# hexagon.net
KiCad netlist of a schematic drawn in EAGLE
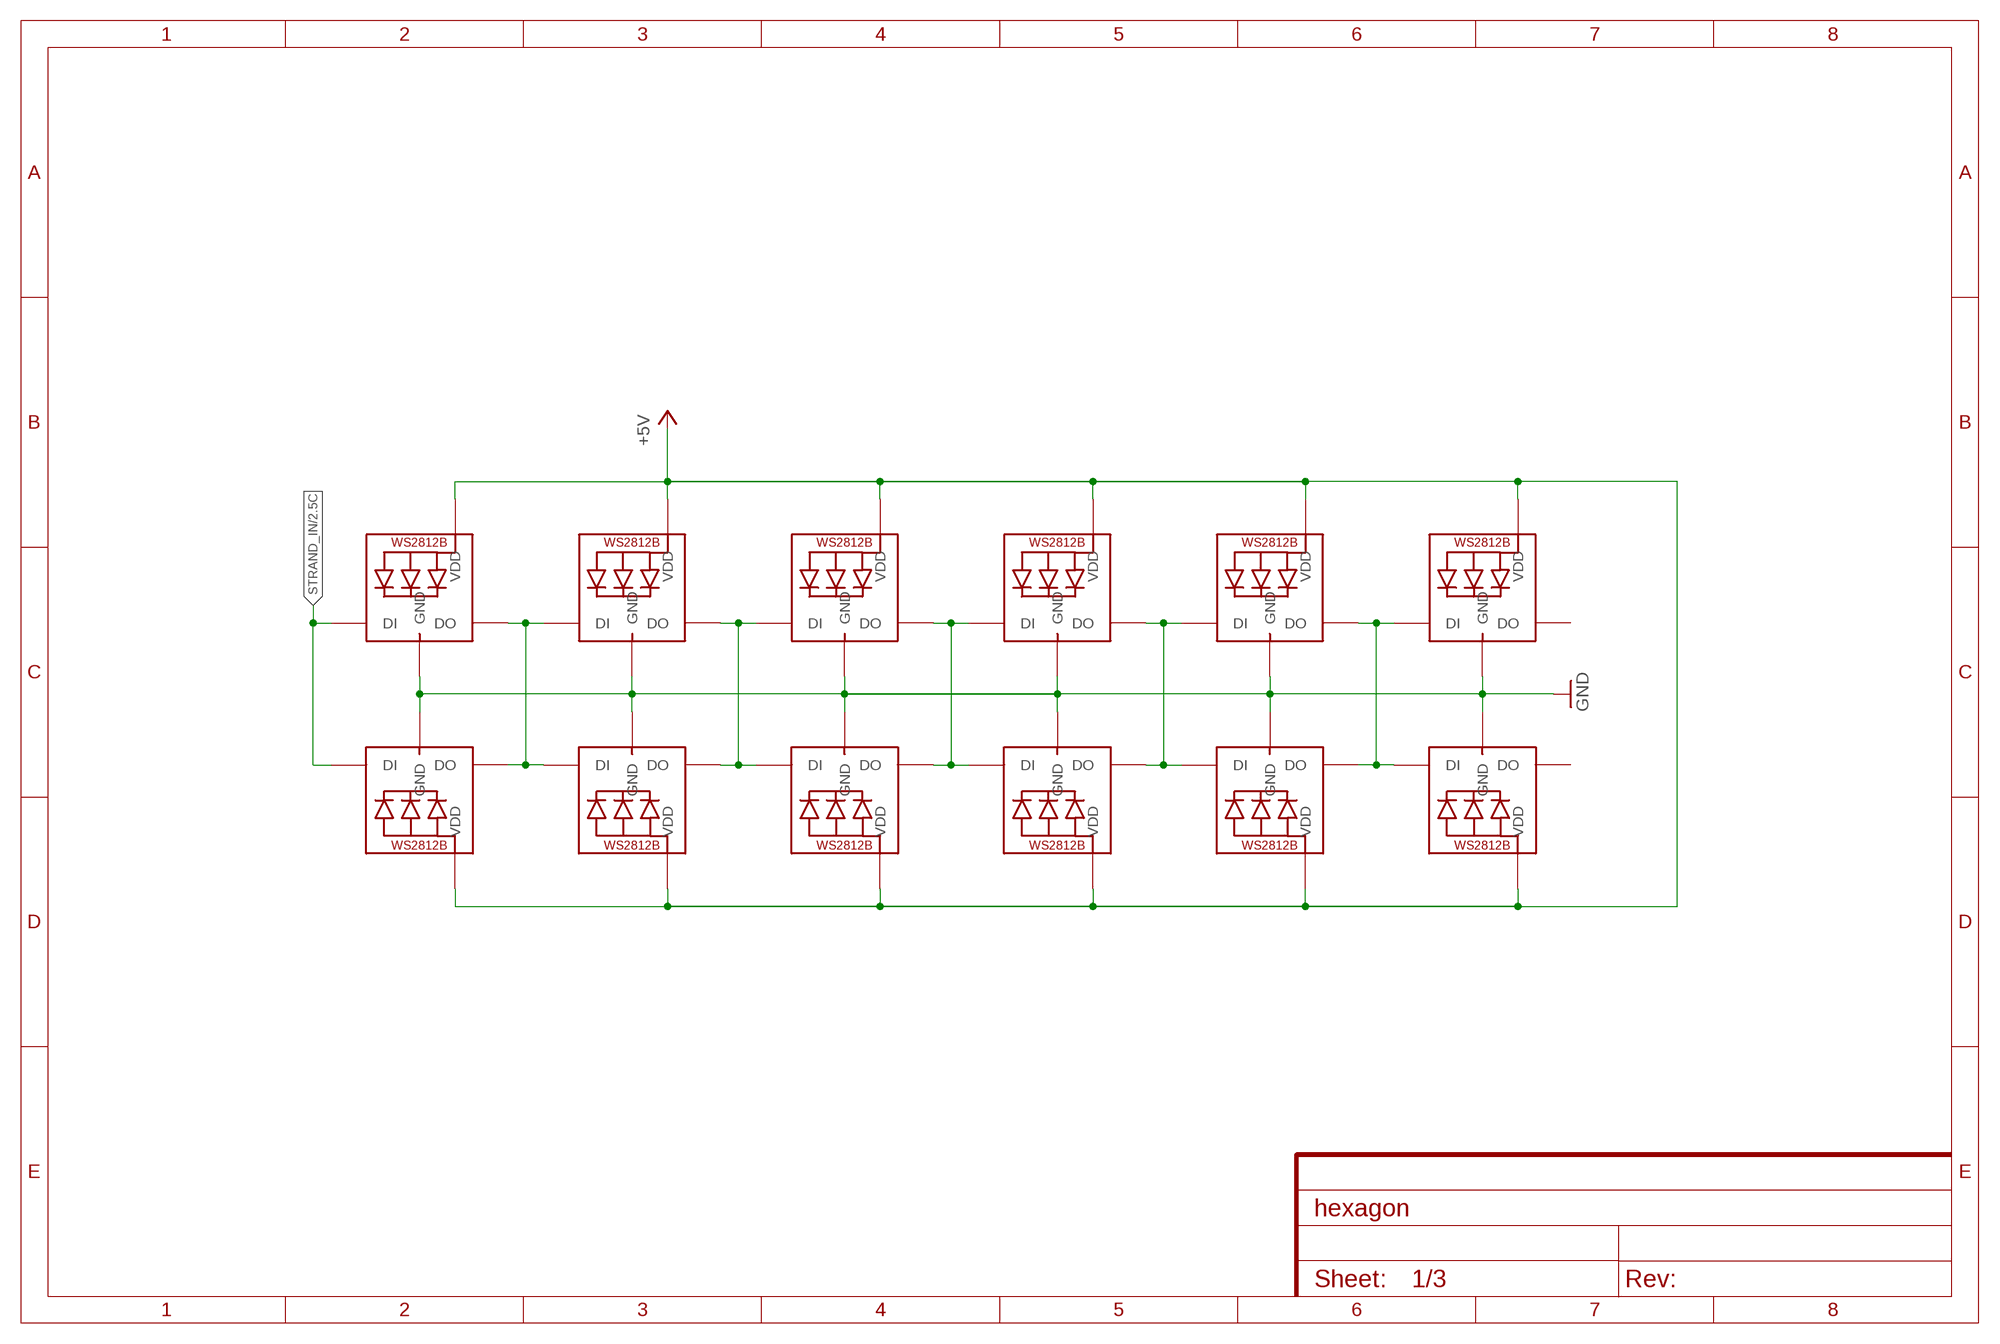
[diagram p0: schematic, sheet 1]
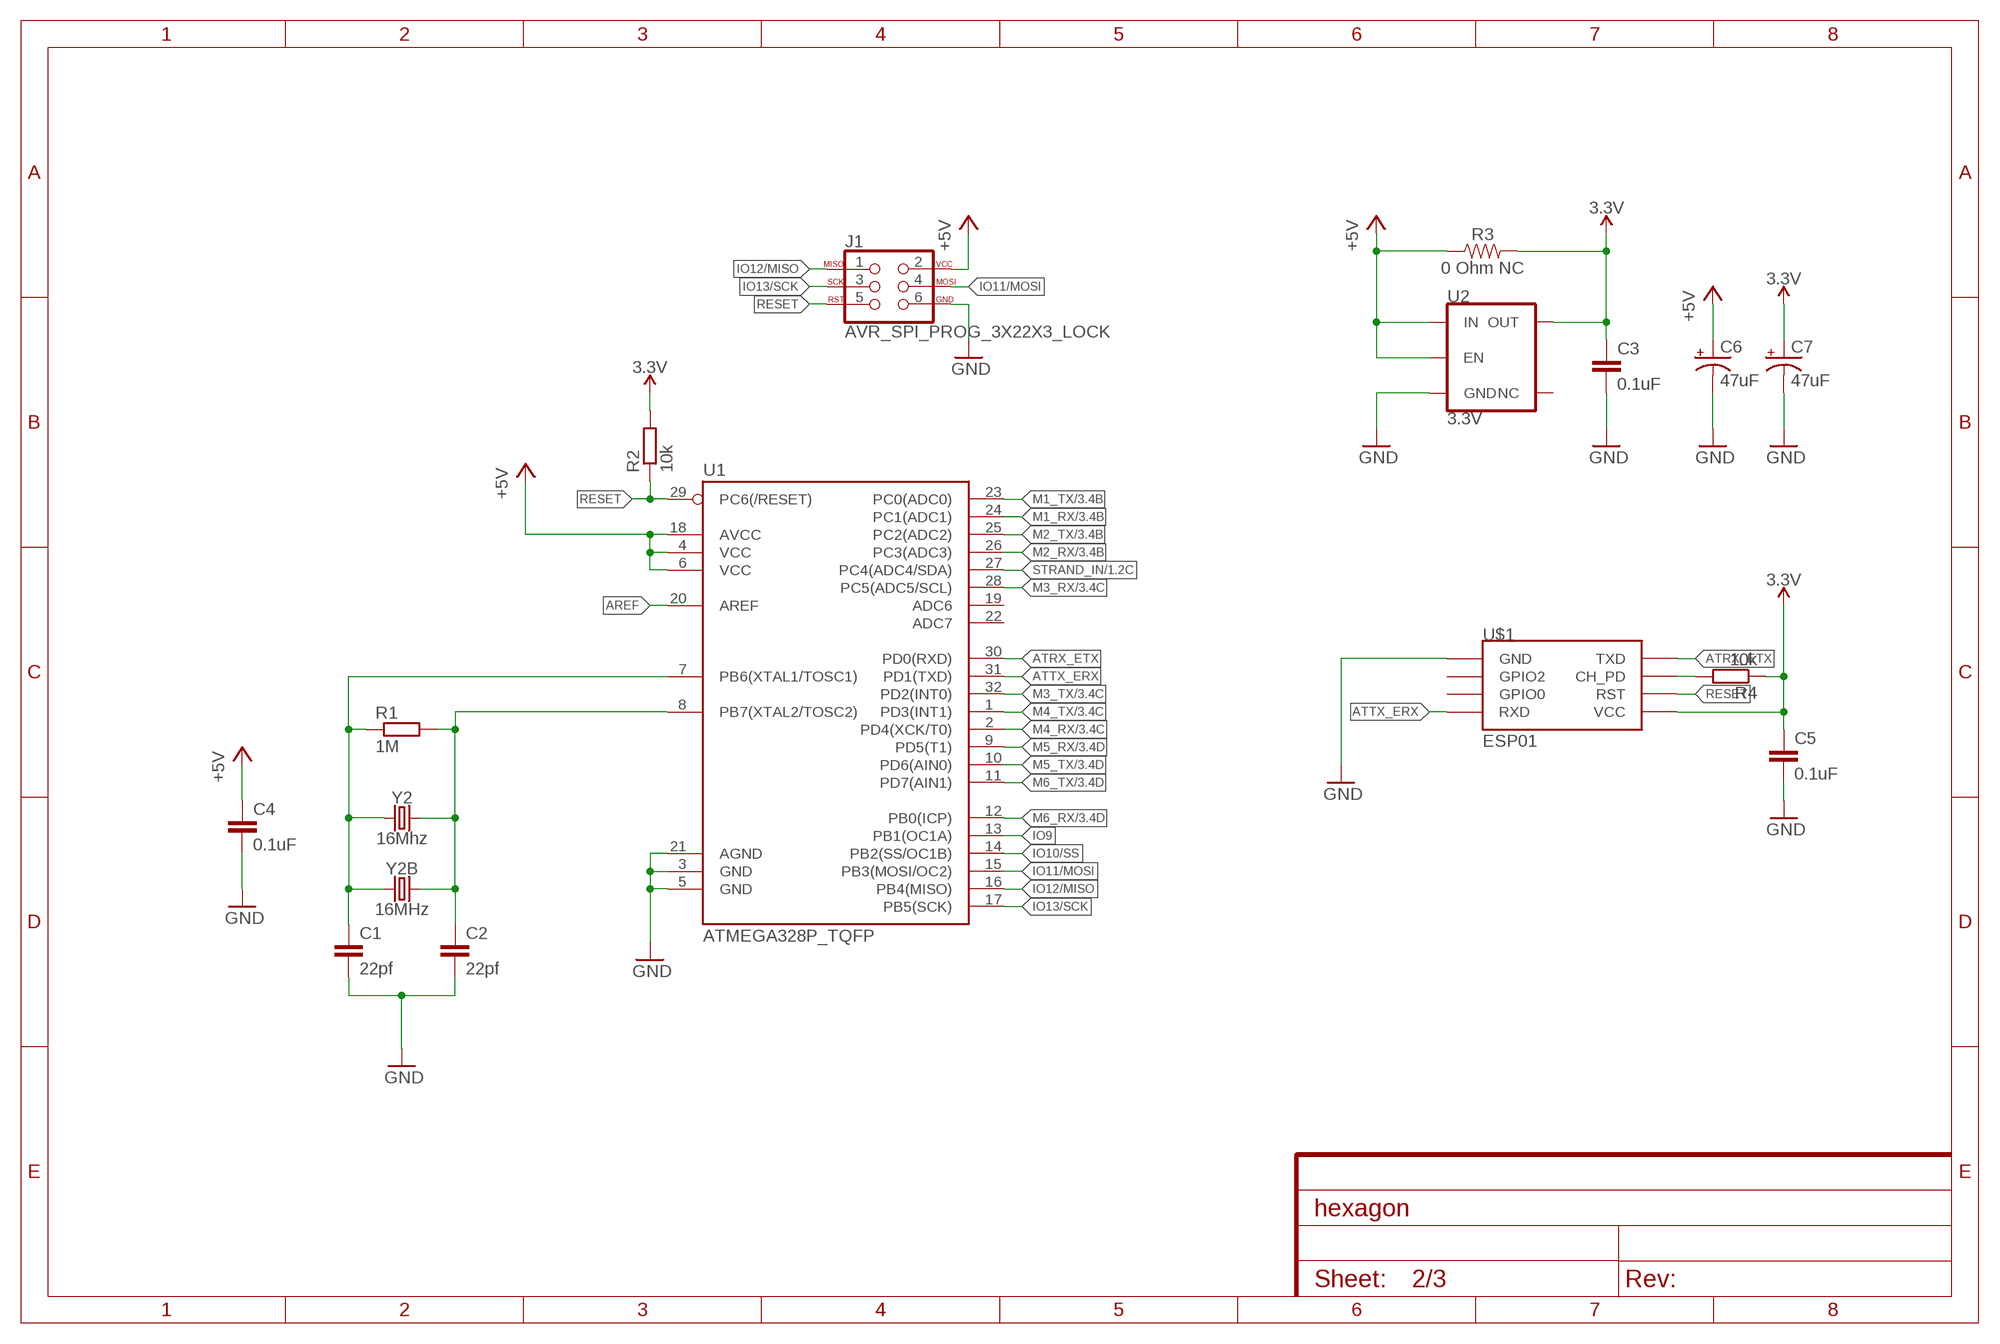
[diagram p1: schematic, sheet 2]
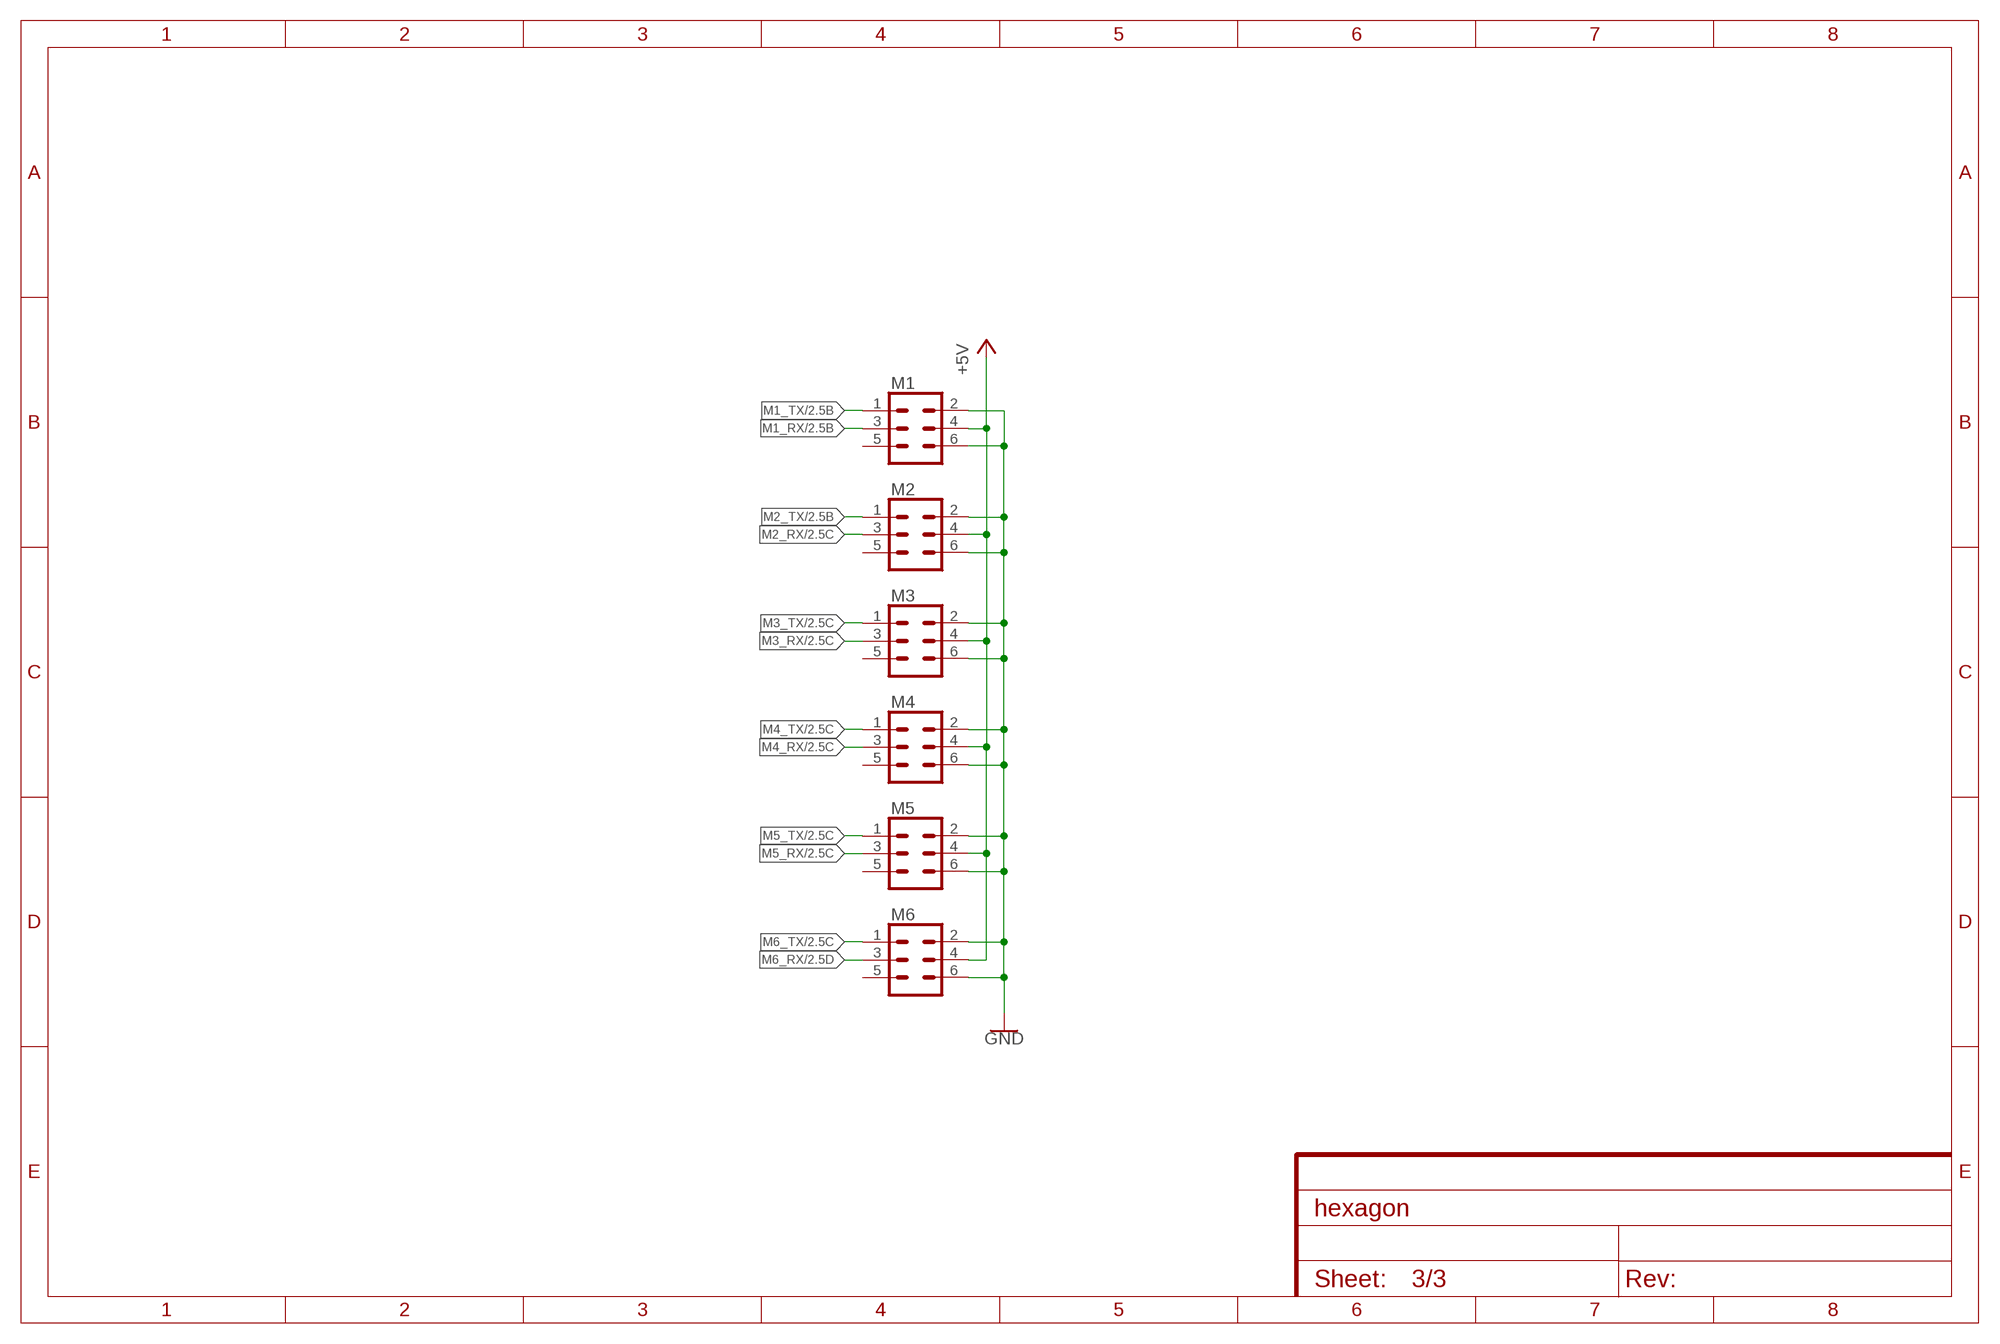
[diagram p2: schematic, sheet 3]

(export (version "E")
  (design (tool "Eeschema 10.0.6"))
  (components
    (comp (ref "C1")
      (value "22pf")
      (footprint "eagle-import:C0603")
      (libsource (lib "eagle-import") (part "C-EUC0603"))
    )
    (comp (ref "C2")
      (value "22pf")
      (footprint "eagle-import:C0603")
      (libsource (lib "eagle-import") (part "C-EUC0603"))
    )
    (comp (ref "C3")
      (value "0.1uF")
      (footprint "eagle-import:C0603")
      (libsource (lib "eagle-import") (part "C-EUC0603"))
    )
    (comp (ref "C4")
      (value "0.1uF")
      (footprint "eagle-import:C0603")
      (libsource (lib "eagle-import") (part "C-EUC0603"))
    )
    (comp (ref "C5")
      (value "0.1uF")
      (footprint "eagle-import:C0603")
      (libsource (lib "eagle-import") (part "C-EUC0603"))
    )
    (comp (ref "C6")
      (value "47uF")
      (footprint "eagle-import:PANASONIC_D")
      (libsource (lib "eagle-import") (part "47UF-POLAR-PANASONIC_D-35V-20%"))
    )
    (comp (ref "C7")
      (value "47uF")
      (footprint "eagle-import:PANASONIC_D")
      (libsource (lib "eagle-import") (part "47UF-POLAR-PANASONIC_D-35V-20%"))
    )
    (comp (ref "J1")
      (value "AVR_SPI_PROG_3X22X3_LOCK")
      (footprint "eagle-import:2X3_LOCK")
      (libsource (lib "eagle-import") (part "AVR_SPI_PROG_3X22X3_LOCK"))
    )
    (comp (ref "R1")
      (value "1M")
      (footprint "eagle-import:R0603")
      (libsource (lib "eagle-import") (part "R-EU_R0603"))
    )
    (comp (ref "R2")
      (value "10k")
      (footprint "eagle-import:R0603")
      (libsource (lib "eagle-import") (part "R-EU_R0603"))
    )
    (comp (ref "R3")
      (value "0 Ohm NC")
      (footprint "eagle-import:0603")
      (libsource (lib "eagle-import") (part "RESISTOR0603"))
    )
    (comp (ref "R4")
      (value "10k")
      (footprint "eagle-import:R0603")
      (libsource (lib "eagle-import") (part "R-EU_R0603"))
    )
    (comp (ref "U$1")
      (value "ESP01")
      (footprint "eagle-import:ESP01")
      (libsource (lib "eagle-import") (part "ESP01"))
    )
    (comp (ref "U1")
      (value "ATMEGA328P_TQFP")
      (footprint "eagle-import:TQFP32-08")
      (libsource (lib "eagle-import") (part "ATMEGA328P_TQFP"))
    )
    (comp (ref "U2")
      (value "3.3V")
      (footprint "eagle-import:SOT23-5")
      (libsource (lib "eagle-import") (part "V_REG_AP2112K-3.3V"))
    )
    (comp (ref "Y2")
      (value "16Mhz")
      (footprint "eagle-import:HC49UP")
      (libsource (lib "eagle-import") (part "CRYSTAL-8MHZSMD-HC49UP"))
    )
    (comp (ref "Y2B")
      (value "16MHz")
      (footprint "eagle-import:HC49U")
      (libsource (lib "eagle-import") (part "CRYSTALPTH-HC49UV"))
    )
    (comp (ref "M1")
      (value "CONN_03X2SHROUD")
      (footprint "eagle-import:2X3-SHROUDED")
      (libsource (lib "eagle-import") (part "CONN_03X2SHROUD"))
    )
    (comp (ref "M2")
      (value "CONN_03X2SHROUD")
      (footprint "eagle-import:2X3-SHROUDED")
      (libsource (lib "eagle-import") (part "CONN_03X2SHROUD"))
    )
    (comp (ref "M3")
      (value "CONN_03X2SHROUD")
      (footprint "eagle-import:2X3-SHROUDED")
      (libsource (lib "eagle-import") (part "CONN_03X2SHROUD"))
    )
    (comp (ref "M4")
      (value "CONN_03X2SHROUD")
      (footprint "eagle-import:2X3-SHROUDED")
      (libsource (lib "eagle-import") (part "CONN_03X2SHROUD"))
    )
    (comp (ref "M5")
      (value "CONN_03X2SHROUD")
      (footprint "eagle-import:2X3-SHROUDED")
      (libsource (lib "eagle-import") (part "CONN_03X2SHROUD"))
    )
    (comp (ref "M6")
      (value "CONN_03X2SHROUD")
      (footprint "eagle-import:2X3-SHROUDED")
      (libsource (lib "eagle-import") (part "CONN_03X2SHROUD"))
    )
    (comp (ref "LED1")
      (value "WS2812B5050")
      (footprint "eagle-import:WS2812B")
      (libsource (lib "eagle-import") (part "WS2812B5050"))
    )
    (comp (ref "LED2")
      (value "WS2812B5050")
      (footprint "eagle-import:WS2812B")
      (libsource (lib "eagle-import") (part "WS2812B5050"))
    )
    (comp (ref "LED3")
      (value "WS2812B5050")
      (footprint "eagle-import:WS2812B")
      (libsource (lib "eagle-import") (part "WS2812B5050"))
    )
    (comp (ref "LED4")
      (value "WS2812B5050")
      (footprint "eagle-import:WS2812B")
      (libsource (lib "eagle-import") (part "WS2812B5050"))
    )
    (comp (ref "LED5")
      (value "WS2812B5050")
      (footprint "eagle-import:WS2812B")
      (libsource (lib "eagle-import") (part "WS2812B5050"))
    )
    (comp (ref "LED6")
      (value "WS2812B5050")
      (footprint "eagle-import:WS2812B")
      (libsource (lib "eagle-import") (part "WS2812B5050"))
    )
    (comp (ref "LED7")
      (value "WS2812B3535")
      (footprint "eagle-import:LED3535")
      (libsource (lib "eagle-import") (part "WS2812B3535"))
    )
    (comp (ref "LED8")
      (value "WS2812B3535")
      (footprint "eagle-import:LED3535")
      (libsource (lib "eagle-import") (part "WS2812B3535"))
    )
    (comp (ref "LED9")
      (value "WS2812B3535")
      (footprint "eagle-import:LED3535")
      (libsource (lib "eagle-import") (part "WS2812B3535"))
    )
    (comp (ref "LED10")
      (value "WS2812B3535")
      (footprint "eagle-import:LED3535")
      (libsource (lib "eagle-import") (part "WS2812B3535"))
    )
    (comp (ref "LED11")
      (value "WS2812B3535")
      (footprint "eagle-import:LED3535")
      (libsource (lib "eagle-import") (part "WS2812B3535"))
    )
    (comp (ref "LED12")
      (value "WS2812B3535")
      (footprint "eagle-import:LED3535")
      (libsource (lib "eagle-import") (part "WS2812B3535"))
    )
  )
  (nets
    (net (code "1") (name "+5V") (class "Default")
      (node (ref "C4") (pin "1") (pinfunction "1_1") (pintype "passive"))
      (node (ref "C6") (pin "+") (pinfunction "+_+") (pintype "passive"))
      (node (ref "J1") (pin "2") (pinfunction "2_2") (pintype "passive"))
      (node (ref "LED1") (pin "1-VDD") (pinfunction "VDD_1-VDD") (pintype "power_in"))
      (node (ref "LED10") (pin "2") (pinfunction "VDD_2") (pintype "power_in"))
      (node (ref "LED11") (pin "2") (pinfunction "VDD_2") (pintype "power_in"))
      (node (ref "LED12") (pin "2") (pinfunction "VDD_2") (pintype "power_in"))
      (node (ref "LED2") (pin "1-VDD") (pinfunction "VDD_1-VDD") (pintype "power_in"))
      (node (ref "LED3") (pin "1-VDD") (pinfunction "VDD_1-VDD") (pintype "power_in"))
      (node (ref "LED4") (pin "1-VDD") (pinfunction "VDD_1-VDD") (pintype "power_in"))
      (node (ref "LED5") (pin "1-VDD") (pinfunction "VDD_1-VDD") (pintype "power_in"))
      (node (ref "LED6") (pin "1-VDD") (pinfunction "VDD_1-VDD") (pintype "power_in"))
      (node (ref "LED7") (pin "2") (pinfunction "VDD_2") (pintype "power_in"))
      (node (ref "LED8") (pin "2") (pinfunction "VDD_2") (pintype "power_in"))
      (node (ref "LED9") (pin "2") (pinfunction "VDD_2") (pintype "power_in"))
      (node (ref "M1") (pin "4") (pinfunction "4_4") (pintype "bidirectional"))
      (node (ref "M2") (pin "4") (pinfunction "4_4") (pintype "bidirectional"))
      (node (ref "M3") (pin "4") (pinfunction "4_4") (pintype "bidirectional"))
      (node (ref "M4") (pin "4") (pinfunction "4_4") (pintype "bidirectional"))
      (node (ref "M5") (pin "4") (pinfunction "4_4") (pintype "bidirectional"))
      (node (ref "M6") (pin "4") (pinfunction "4_4") (pintype "bidirectional"))
      (node (ref "R3") (pin "1") (pinfunction "1_1") (pintype "passive"))
      (node (ref "U1") (pin "18") (pinfunction "AVCC_18") (pintype "bidirectional"))
      (node (ref "U1") (pin "4") (pinfunction "VCC_4") (pintype "bidirectional"))
      (node (ref "U1") (pin "6") (pinfunction "VCC_6") (pintype "bidirectional"))
      (node (ref "U2") (pin "1") (pinfunction "IN_1") (pintype "input"))
      (node (ref "U2") (pin "3") (pinfunction "EN_3") (pintype "input"))
    )
    (net (code "2") (name "3.3V") (class "Default")
      (node (ref "C3") (pin "1") (pinfunction "1_1") (pintype "passive"))
      (node (ref "C5") (pin "1") (pinfunction "1_1") (pintype "passive"))
      (node (ref "C7") (pin "+") (pinfunction "+_+") (pintype "passive"))
      (node (ref "R2") (pin "2") (pinfunction "2_2") (pintype "passive"))
      (node (ref "R3") (pin "2") (pinfunction "2_2") (pintype "passive"))
      (node (ref "R4") (pin "1") (pinfunction "1_1") (pintype "passive"))
      (node (ref "U$1") (pin "VCC") (pinfunction "VCC_VCC") (pintype "bidirectional"))
      (node (ref "U2") (pin "5") (pinfunction "OUT_5") (pintype "passive"))
    )
    (net (code "3") (name "AREF") (class "Default")
      (node (ref "U1") (pin "20") (pinfunction "AREF_20") (pintype "bidirectional"))
    )
    (net (code "4") (name "ATRX_ETX") (class "Default")
      (node (ref "U$1") (pin "TX") (pinfunction "TXD_TX") (pintype "bidirectional"))
      (node (ref "U1") (pin "30") (pinfunction "PD0(RXD)_30") (pintype "bidirectional"))
    )
    (net (code "5") (name "ATTX_ERX") (class "Default")
      (node (ref "U$1") (pin "RX") (pinfunction "RXD_RX") (pintype "bidirectional"))
      (node (ref "U1") (pin "31") (pinfunction "PD1(TXD)_31") (pintype "bidirectional"))
    )
    (net (code "6") (name "GND") (class "Default")
      (node (ref "C1") (pin "2") (pinfunction "2_2") (pintype "passive"))
      (node (ref "C2") (pin "2") (pinfunction "2_2") (pintype "passive"))
      (node (ref "C3") (pin "2") (pinfunction "2_2") (pintype "passive"))
      (node (ref "C4") (pin "2") (pinfunction "2_2") (pintype "passive"))
      (node (ref "C5") (pin "2") (pinfunction "2_2") (pintype "passive"))
      (node (ref "C6") (pin "-") (pinfunction "-_-") (pintype "passive"))
      (node (ref "C7") (pin "-") (pinfunction "-_-") (pintype "passive"))
      (node (ref "J1") (pin "6") (pinfunction "6_6") (pintype "passive"))
      (node (ref "LED1") (pin "3-GND") (pinfunction "GND_3-GND") (pintype "power_in"))
      (node (ref "LED10") (pin "4") (pinfunction "GND_4") (pintype "power_in"))
      (node (ref "LED11") (pin "4") (pinfunction "GND_4") (pintype "power_in"))
      (node (ref "LED12") (pin "4") (pinfunction "GND_4") (pintype "power_in"))
      (node (ref "LED2") (pin "3-GND") (pinfunction "GND_3-GND") (pintype "power_in"))
      (node (ref "LED3") (pin "3-GND") (pinfunction "GND_3-GND") (pintype "power_in"))
      (node (ref "LED4") (pin "3-GND") (pinfunction "GND_3-GND") (pintype "power_in"))
      (node (ref "LED5") (pin "3-GND") (pinfunction "GND_3-GND") (pintype "power_in"))
      (node (ref "LED6") (pin "3-GND") (pinfunction "GND_3-GND") (pintype "power_in"))
      (node (ref "LED7") (pin "4") (pinfunction "GND_4") (pintype "power_in"))
      (node (ref "LED8") (pin "4") (pinfunction "GND_4") (pintype "power_in"))
      (node (ref "LED9") (pin "4") (pinfunction "GND_4") (pintype "power_in"))
      (node (ref "M1") (pin "2") (pinfunction "2_2") (pintype "bidirectional"))
      (node (ref "M1") (pin "6") (pinfunction "6_6") (pintype "bidirectional"))
      (node (ref "M2") (pin "2") (pinfunction "2_2") (pintype "bidirectional"))
      (node (ref "M2") (pin "6") (pinfunction "6_6") (pintype "bidirectional"))
      (node (ref "M3") (pin "2") (pinfunction "2_2") (pintype "bidirectional"))
      (node (ref "M3") (pin "6") (pinfunction "6_6") (pintype "bidirectional"))
      (node (ref "M4") (pin "2") (pinfunction "2_2") (pintype "bidirectional"))
      (node (ref "M4") (pin "6") (pinfunction "6_6") (pintype "bidirectional"))
      (node (ref "M5") (pin "2") (pinfunction "2_2") (pintype "bidirectional"))
      (node (ref "M5") (pin "6") (pinfunction "6_6") (pintype "bidirectional"))
      (node (ref "M6") (pin "2") (pinfunction "2_2") (pintype "bidirectional"))
      (node (ref "M6") (pin "6") (pinfunction "6_6") (pintype "bidirectional"))
      (node (ref "U$1") (pin "GND") (pinfunction "GND_GND") (pintype "bidirectional"))
      (node (ref "U1") (pin "21") (pinfunction "AGND_21") (pintype "bidirectional"))
      (node (ref "U1") (pin "3") (pinfunction "GND_3") (pintype "bidirectional"))
      (node (ref "U1") (pin "5") (pinfunction "GND_5") (pintype "bidirectional"))
      (node (ref "U2") (pin "2") (pinfunction "GND_2") (pintype "input"))
    )
    (net (code "7") (name "IO9") (class "Default")
      (node (ref "U1") (pin "13") (pinfunction "PB1(OC1A)_13") (pintype "bidirectional"))
    )
    (net (code "8") (name "IO10{slash}SS") (class "Default")
      (node (ref "U1") (pin "14") (pinfunction "PB2(SS/OC1B)_14") (pintype "bidirectional"))
    )
    (net (code "9") (name "IO11{slash}MOSI") (class "Default")
      (node (ref "J1") (pin "4") (pinfunction "4_4") (pintype "passive"))
      (node (ref "U1") (pin "15") (pinfunction "PB3(MOSI/OC2)_15") (pintype "bidirectional"))
    )
    (net (code "10") (name "IO12{slash}MISO") (class "Default")
      (node (ref "J1") (pin "1") (pinfunction "1_1") (pintype "passive"))
      (node (ref "U1") (pin "16") (pinfunction "PB4(MISO)_16") (pintype "bidirectional"))
    )
    (net (code "11") (name "IO13{slash}SCK") (class "Default")
      (node (ref "J1") (pin "3") (pinfunction "3_3") (pintype "passive"))
      (node (ref "U1") (pin "17") (pinfunction "PB5(SCK)_17") (pintype "bidirectional"))
    )
    (net (code "12") (name "M1_RX") (class "Default")
      (node (ref "M1") (pin "3") (pinfunction "3_3") (pintype "bidirectional"))
      (node (ref "U1") (pin "24") (pinfunction "PC1(ADC1)_24") (pintype "bidirectional"))
    )
    (net (code "13") (name "M1_TX") (class "Default")
      (node (ref "M1") (pin "1") (pinfunction "1_1") (pintype "bidirectional"))
      (node (ref "U1") (pin "23") (pinfunction "PC0(ADC0)_23") (pintype "bidirectional"))
    )
    (net (code "14") (name "M2_RX") (class "Default")
      (node (ref "M2") (pin "3") (pinfunction "3_3") (pintype "bidirectional"))
      (node (ref "U1") (pin "26") (pinfunction "PC3(ADC3)_26") (pintype "bidirectional"))
    )
    (net (code "15") (name "M2_TX") (class "Default")
      (node (ref "M2") (pin "1") (pinfunction "1_1") (pintype "bidirectional"))
      (node (ref "U1") (pin "25") (pinfunction "PC2(ADC2)_25") (pintype "bidirectional"))
    )
    (net (code "16") (name "M3_RX") (class "Default")
      (node (ref "M3") (pin "3") (pinfunction "3_3") (pintype "bidirectional"))
      (node (ref "U1") (pin "28") (pinfunction "PC5(ADC5/SCL)_28") (pintype "bidirectional"))
    )
    (net (code "17") (name "M3_TX") (class "Default")
      (node (ref "M3") (pin "1") (pinfunction "1_1") (pintype "bidirectional"))
      (node (ref "U1") (pin "32") (pinfunction "PD2(INT0)_32") (pintype "bidirectional"))
    )
    (net (code "18") (name "M4_RX") (class "Default")
      (node (ref "M4") (pin "3") (pinfunction "3_3") (pintype "bidirectional"))
      (node (ref "U1") (pin "2") (pinfunction "PD4(XCK/T0)_2") (pintype "bidirectional"))
    )
    (net (code "19") (name "M4_TX") (class "Default")
      (node (ref "M4") (pin "1") (pinfunction "1_1") (pintype "bidirectional"))
      (node (ref "U1") (pin "1") (pinfunction "PD3(INT1)_1") (pintype "bidirectional"))
    )
    (net (code "20") (name "M5_RX") (class "Default")
      (node (ref "M5") (pin "3") (pinfunction "3_3") (pintype "bidirectional"))
      (node (ref "U1") (pin "9") (pinfunction "PD5(T1)_9") (pintype "bidirectional"))
    )
    (net (code "21") (name "M5_TX") (class "Default")
      (node (ref "M5") (pin "1") (pinfunction "1_1") (pintype "bidirectional"))
      (node (ref "U1") (pin "10") (pinfunction "PD6(AIN0)_10") (pintype "bidirectional"))
    )
    (net (code "22") (name "M6_RX") (class "Default")
      (node (ref "M6") (pin "3") (pinfunction "3_3") (pintype "bidirectional"))
      (node (ref "U1") (pin "12") (pinfunction "PB0(ICP)_12") (pintype "bidirectional"))
    )
    (net (code "23") (name "M6_TX") (class "Default")
      (node (ref "M6") (pin "1") (pinfunction "1_1") (pintype "bidirectional"))
      (node (ref "U1") (pin "11") (pinfunction "PD7(AIN1)_11") (pintype "bidirectional"))
    )
    (net (code "24") (name "Net-(LED1-DI)") (class "Default")
      (node (ref "LED1") (pin "4-DIN") (pinfunction "DI_4-DIN") (pintype "input"))
      (node (ref "LED12") (pin "3") (pinfunction "DO_3") (pintype "output"))
      (node (ref "LED6") (pin "2-DOUT") (pinfunction "DO_2-DOUT") (pintype "output"))
      (node (ref "LED7") (pin "1") (pinfunction "DI_1") (pintype "input"))
    )
    (net (code "25") (name "Net-(LED2-DO)") (class "Default")
      (node (ref "LED2") (pin "2-DOUT") (pinfunction "DO_2-DOUT") (pintype "output"))
      (node (ref "LED3") (pin "4-DIN") (pinfunction "DI_4-DIN") (pintype "input"))
      (node (ref "LED8") (pin "3") (pinfunction "DO_3") (pintype "output"))
      (node (ref "LED9") (pin "1") (pinfunction "DI_1") (pintype "input"))
    )
    (net (code "26") (name "Net-(LED10-DI)") (class "Default")
      (node (ref "LED10") (pin "1") (pinfunction "DI_1") (pintype "input"))
      (node (ref "LED3") (pin "2-DOUT") (pinfunction "DO_2-DOUT") (pintype "output"))
      (node (ref "LED4") (pin "4-DIN") (pinfunction "DI_4-DIN") (pintype "input"))
      (node (ref "LED9") (pin "3") (pinfunction "DO_3") (pintype "output"))
    )
    (net (code "27") (name "Net-(LED10-DO)") (class "Default")
      (node (ref "LED10") (pin "3") (pinfunction "DO_3") (pintype "output"))
      (node (ref "LED11") (pin "1") (pinfunction "DI_1") (pintype "input"))
      (node (ref "LED4") (pin "2-DOUT") (pinfunction "DO_2-DOUT") (pintype "output"))
      (node (ref "LED5") (pin "4-DIN") (pinfunction "DI_4-DIN") (pintype "input"))
    )
    (net (code "28") (name "Net-(LED11-DO)") (class "Default")
      (node (ref "LED11") (pin "3") (pinfunction "DO_3") (pintype "output"))
      (node (ref "LED12") (pin "1") (pinfunction "DI_1") (pintype "input"))
      (node (ref "LED5") (pin "2-DOUT") (pinfunction "DO_2-DOUT") (pintype "output"))
      (node (ref "LED6") (pin "4-DIN") (pinfunction "DI_4-DIN") (pintype "input"))
    )
    (net (code "29") (name "Net-(R4-Pad2)") (class "Default")
      (node (ref "R4") (pin "2") (pinfunction "2_2") (pintype "passive"))
      (node (ref "U$1") (pin "CH_PD") (pinfunction "CH_PD_CH_PD") (pintype "bidirectional"))
    )
    (net (code "30") (name "Net-(U1-PB6(XTAL1{slash}TOSC1))") (class "Default")
      (node (ref "C1") (pin "1") (pinfunction "1_1") (pintype "passive"))
      (node (ref "R1") (pin "1") (pinfunction "1_1") (pintype "passive"))
      (node (ref "U1") (pin "7") (pinfunction "PB6(XTAL1/TOSC1)_7") (pintype "bidirectional"))
      (node (ref "Y2") (pin "1") (pinfunction "1_1") (pintype "passive"))
      (node (ref "Y2B") (pin "1") (pinfunction "1_1") (pintype "passive"))
    )
    (net (code "31") (name "Net-(U1-PB7(XTAL2{slash}TOSC2))") (class "Default")
      (node (ref "C2") (pin "1") (pinfunction "1_1") (pintype "passive"))
      (node (ref "R1") (pin "2") (pinfunction "2_2") (pintype "passive"))
      (node (ref "U1") (pin "8") (pinfunction "PB7(XTAL2/TOSC2)_8") (pintype "bidirectional"))
      (node (ref "Y2") (pin "2") (pinfunction "2_2") (pintype "passive"))
      (node (ref "Y2B") (pin "2") (pinfunction "2_2") (pintype "passive"))
    )
    (net (code "32") (name "RESET") (class "Default")
      (node (ref "J1") (pin "5") (pinfunction "5_5") (pintype "passive"))
      (node (ref "R2") (pin "1") (pinfunction "1_1") (pintype "passive"))
      (node (ref "U$1") (pin "RST") (pinfunction "RST_RST") (pintype "bidirectional"))
      (node (ref "U1") (pin "29") (pinfunction "PC6(/RESET)_29") (pintype "bidirectional"))
    )
    (net (code "33") (name "STRAND_IN") (class "Default")
      (node (ref "LED2") (pin "4-DIN") (pinfunction "DI_4-DIN") (pintype "input"))
      (node (ref "LED8") (pin "1") (pinfunction "DI_1") (pintype "input"))
      (node (ref "U1") (pin "27") (pinfunction "PC4(ADC4/SDA)_27") (pintype "bidirectional"))
    )
    (net (code "34") (name "unconnected-(LED1-DO-Pad2-DOUT)") (class "Default")
      (node (ref "LED1") (pin "2-DOUT") (pinfunction "DO_2-DOUT") (pintype "output"))
    )
    (net (code "35") (name "unconnected-(LED7-DO-Pad3)") (class "Default")
      (node (ref "LED7") (pin "3") (pinfunction "DO_3") (pintype "output"))
    )
    (net (code "36") (name "unconnected-(M1-Pad5)") (class "Default")
      (node (ref "M1") (pin "5") (pinfunction "5_5") (pintype "bidirectional"))
    )
    (net (code "37") (name "unconnected-(M2-Pad5)") (class "Default")
      (node (ref "M2") (pin "5") (pinfunction "5_5") (pintype "bidirectional"))
    )
    (net (code "38") (name "unconnected-(M3-Pad5)") (class "Default")
      (node (ref "M3") (pin "5") (pinfunction "5_5") (pintype "bidirectional"))
    )
    (net (code "39") (name "unconnected-(M4-Pad5)") (class "Default")
      (node (ref "M4") (pin "5") (pinfunction "5_5") (pintype "bidirectional"))
    )
    (net (code "40") (name "unconnected-(M5-Pad5)") (class "Default")
      (node (ref "M5") (pin "5") (pinfunction "5_5") (pintype "bidirectional"))
    )
    (net (code "41") (name "unconnected-(M6-Pad5)") (class "Default")
      (node (ref "M6") (pin "5") (pinfunction "5_5") (pintype "bidirectional"))
    )
    (net (code "42") (name "unconnected-(U$1-PadGPIO0)") (class "Default")
      (node (ref "U$1") (pin "GPIO0") (pinfunction "GPIO0_GPIO0") (pintype "bidirectional"))
    )
    (net (code "43") (name "unconnected-(U$1-PadGPIO2)") (class "Default")
      (node (ref "U$1") (pin "GPIO2") (pinfunction "GPIO2_GPIO2") (pintype "bidirectional"))
    )
    (net (code "44") (name "unconnected-(U1-ADC6-Pad19)") (class "Default")
      (node (ref "U1") (pin "19") (pinfunction "ADC6_19") (pintype "bidirectional"))
    )
    (net (code "45") (name "unconnected-(U1-ADC7-Pad22)") (class "Default")
      (node (ref "U1") (pin "22") (pinfunction "ADC7_22") (pintype "bidirectional"))
    )
    (net (code "46") (name "unconnected-(U2-NC-Pad4)") (class "Default")
      (node (ref "U2") (pin "4") (pinfunction "NC_4") (pintype "no_connect"))
    )
  )
)
